# Sheet1.net
KiCad netlist of a schematic drawn in Altium Designer
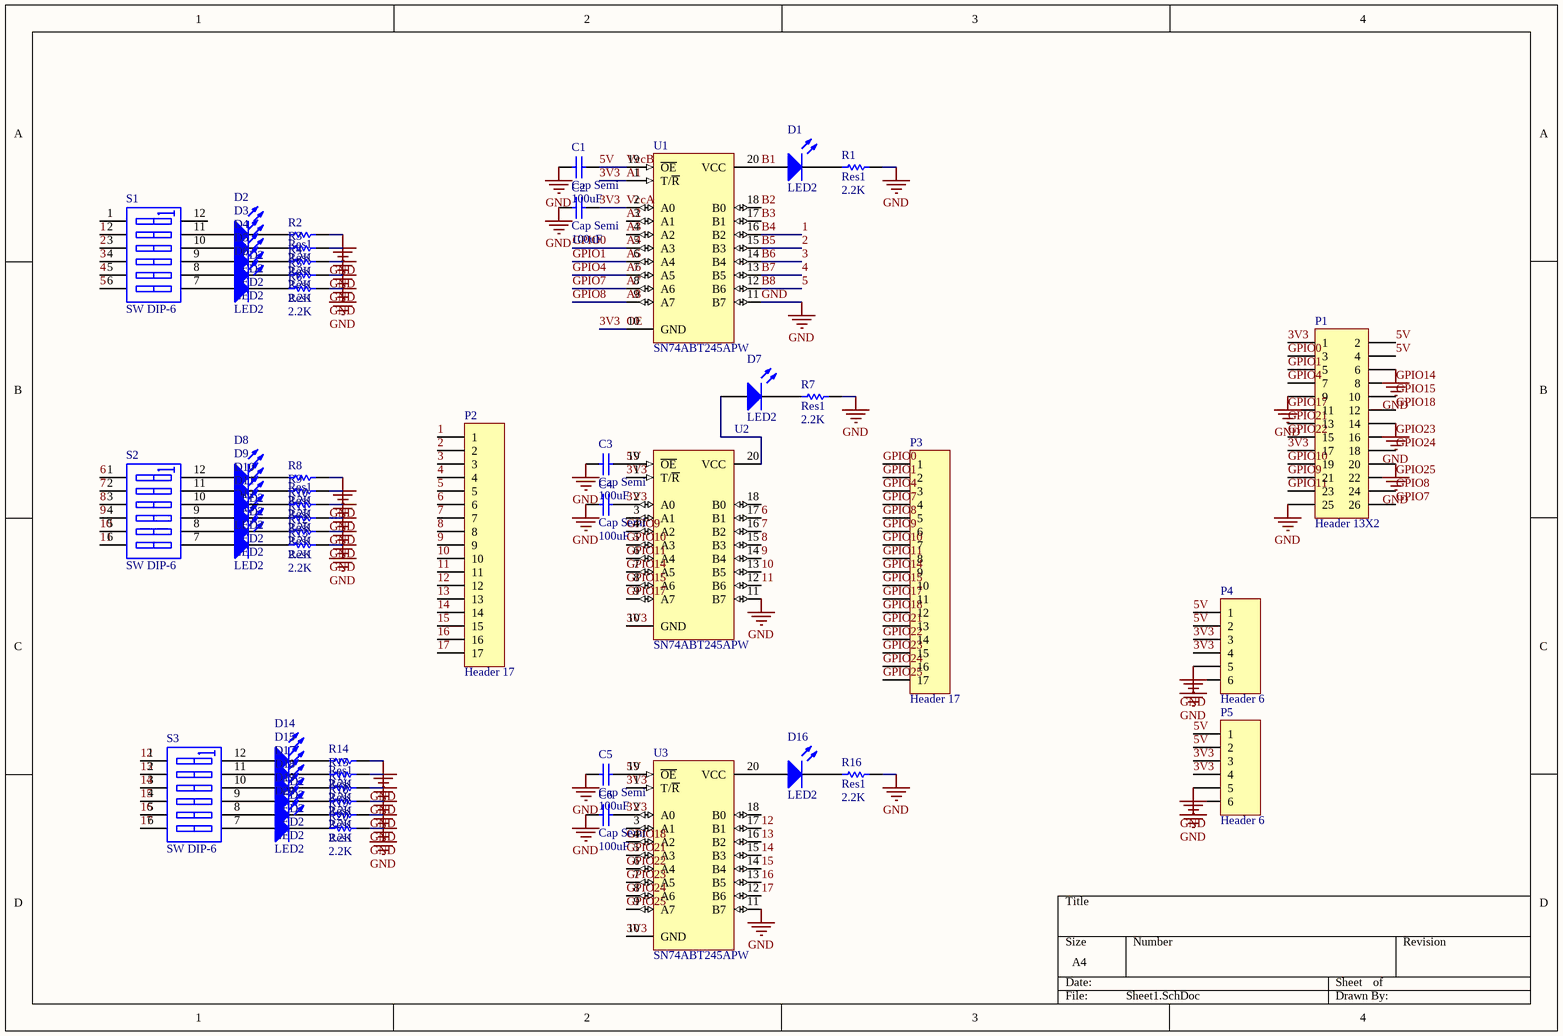
[diagram p0: Sheet1.SchDoc]

(export (version "E")
  (design (tool "Eeschema 10.0.6"))
  (components
    (comp (ref "C1")
      (value "Cap Semi")
      (footprint "C1206")
      (description "Capacitor (Semiconductor SIM Model)")
      (fields (field (name "ALTIUM_VALUE") "100uF") (field (name "PUBLISHER") "Altium Limited"))
      (libsource (lib "Miscellaneous Devices") (part "Cap Semi"))
    )
    (comp (ref "C2")
      (value "Cap Semi")
      (footprint "C1206")
      (description "Capacitor (Semiconductor SIM Model)")
      (fields (field (name "ALTIUM_VALUE") "100uF") (field (name "PUBLISHER") "Altium Limited"))
      (libsource (lib "Miscellaneous Devices") (part "Cap Semi"))
    )
    (comp (ref "C3")
      (value "Cap Semi")
      (footprint "C1206")
      (description "Capacitor (Semiconductor SIM Model)")
      (fields (field (name "ALTIUM_VALUE") "100uF") (field (name "PUBLISHER") "Altium Limited"))
      (libsource (lib "Miscellaneous Devices") (part "Cap Semi"))
    )
    (comp (ref "C4")
      (value "Cap Semi")
      (footprint "C1206")
      (description "Capacitor (Semiconductor SIM Model)")
      (fields (field (name "ALTIUM_VALUE") "100uF") (field (name "PUBLISHER") "Altium Limited"))
      (libsource (lib "Miscellaneous Devices") (part "Cap Semi"))
    )
    (comp (ref "C5")
      (value "Cap Semi")
      (footprint "C1206")
      (description "Capacitor (Semiconductor SIM Model)")
      (fields (field (name "ALTIUM_VALUE") "100uF") (field (name "PUBLISHER") "Altium Limited"))
      (libsource (lib "Miscellaneous Devices") (part "Cap Semi"))
    )
    (comp (ref "C6")
      (value "Cap Semi")
      (footprint "C1206")
      (description "Capacitor (Semiconductor SIM Model)")
      (fields (field (name "ALTIUM_VALUE") "100uF") (field (name "PUBLISHER") "Altium Limited"))
      (libsource (lib "Miscellaneous Devices") (part "Cap Semi"))
    )
    (comp (ref "D1")
      (value "LED2")
      (footprint "0603")
      (description "Typical RED, GREEN, YELLOW, AMBER GaAs LED")
      (fields (field (name "PUBLISHER") "Altium Limited"))
      (libsource (lib "Miscellaneous Devices") (part "LED2"))
    )
    (comp (ref "D2")
      (value "LED2")
      (footprint "0603")
      (description "Typical RED, GREEN, YELLOW, AMBER GaAs LED")
      (fields (field (name "PUBLISHER") "Altium Limited"))
      (libsource (lib "Miscellaneous Devices") (part "LED2"))
    )
    (comp (ref "D3")
      (value "LED2")
      (footprint "0603")
      (description "Typical RED, GREEN, YELLOW, AMBER GaAs LED")
      (fields (field (name "PUBLISHER") "Altium Limited"))
      (libsource (lib "Miscellaneous Devices") (part "LED2"))
    )
    (comp (ref "D4")
      (value "LED2")
      (footprint "0603")
      (description "Typical RED, GREEN, YELLOW, AMBER GaAs LED")
      (fields (field (name "PUBLISHER") "Altium Limited"))
      (libsource (lib "Miscellaneous Devices") (part "LED2"))
    )
    (comp (ref "D5")
      (value "LED2")
      (footprint "0603")
      (description "Typical RED, GREEN, YELLOW, AMBER GaAs LED")
      (fields (field (name "PUBLISHER") "Altium Limited"))
      (libsource (lib "Miscellaneous Devices") (part "LED2"))
    )
    (comp (ref "D6")
      (value "LED2")
      (footprint "0603")
      (description "Typical RED, GREEN, YELLOW, AMBER GaAs LED")
      (fields (field (name "PUBLISHER") "Altium Limited"))
      (libsource (lib "Miscellaneous Devices") (part "LED2"))
    )
    (comp (ref "D7")
      (value "LED2")
      (footprint "0603")
      (description "Typical RED, GREEN, YELLOW, AMBER GaAs LED")
      (fields (field (name "PUBLISHER") "Altium Limited"))
      (libsource (lib "Miscellaneous Devices") (part "LED2"))
    )
    (comp (ref "D8")
      (value "LED2")
      (footprint "0603")
      (description "Typical RED, GREEN, YELLOW, AMBER GaAs LED")
      (fields (field (name "PUBLISHER") "Altium Limited"))
      (libsource (lib "Miscellaneous Devices") (part "LED2"))
    )
    (comp (ref "D9")
      (value "LED2")
      (footprint "0603")
      (description "Typical RED, GREEN, YELLOW, AMBER GaAs LED")
      (fields (field (name "PUBLISHER") "Altium Limited"))
      (libsource (lib "Miscellaneous Devices") (part "LED2"))
    )
    (comp (ref "D10")
      (value "LED2")
      (footprint "0603")
      (description "Typical RED, GREEN, YELLOW, AMBER GaAs LED")
      (fields (field (name "PUBLISHER") "Altium Limited"))
      (libsource (lib "Miscellaneous Devices") (part "LED2"))
    )
    (comp (ref "D11")
      (value "LED2")
      (footprint "0603")
      (description "Typical RED, GREEN, YELLOW, AMBER GaAs LED")
      (fields (field (name "PUBLISHER") "Altium Limited"))
      (libsource (lib "Miscellaneous Devices") (part "LED2"))
    )
    (comp (ref "D12")
      (value "LED2")
      (footprint "0603")
      (description "Typical RED, GREEN, YELLOW, AMBER GaAs LED")
      (fields (field (name "PUBLISHER") "Altium Limited"))
      (libsource (lib "Miscellaneous Devices") (part "LED2"))
    )
    (comp (ref "D13")
      (value "LED2")
      (footprint "0603")
      (description "Typical RED, GREEN, YELLOW, AMBER GaAs LED")
      (fields (field (name "PUBLISHER") "Altium Limited"))
      (libsource (lib "Miscellaneous Devices") (part "LED2"))
    )
    (comp (ref "D14")
      (value "LED2")
      (footprint "0603")
      (description "Typical RED, GREEN, YELLOW, AMBER GaAs LED")
      (fields (field (name "PUBLISHER") "Altium Limited"))
      (libsource (lib "Miscellaneous Devices") (part "LED2"))
    )
    (comp (ref "D15")
      (value "LED2")
      (footprint "0603")
      (description "Typical RED, GREEN, YELLOW, AMBER GaAs LED")
      (fields (field (name "PUBLISHER") "Altium Limited"))
      (libsource (lib "Miscellaneous Devices") (part "LED2"))
    )
    (comp (ref "D16")
      (value "LED2")
      (footprint "0603")
      (description "Typical RED, GREEN, YELLOW, AMBER GaAs LED")
      (fields (field (name "PUBLISHER") "Altium Limited"))
      (libsource (lib "Miscellaneous Devices") (part "LED2"))
    )
    (comp (ref "D17")
      (value "LED2")
      (footprint "0603")
      (description "Typical RED, GREEN, YELLOW, AMBER GaAs LED")
      (fields (field (name "PUBLISHER") "Altium Limited"))
      (libsource (lib "Miscellaneous Devices") (part "LED2"))
    )
    (comp (ref "D18")
      (value "LED2")
      (footprint "0603")
      (description "Typical RED, GREEN, YELLOW, AMBER GaAs LED")
      (fields (field (name "PUBLISHER") "Altium Limited"))
      (libsource (lib "Miscellaneous Devices") (part "LED2"))
    )
    (comp (ref "D19")
      (value "LED2")
      (footprint "0603")
      (description "Typical RED, GREEN, YELLOW, AMBER GaAs LED")
      (fields (field (name "PUBLISHER") "Altium Limited"))
      (libsource (lib "Miscellaneous Devices") (part "LED2"))
    )
    (comp (ref "D20")
      (value "LED2")
      (footprint "0603")
      (description "Typical RED, GREEN, YELLOW, AMBER GaAs LED")
      (fields (field (name "PUBLISHER") "Altium Limited"))
      (libsource (lib "Miscellaneous Devices") (part "LED2"))
    )
    (comp (ref "P1")
      (value "Header 13X2")
      (footprint "HDR2X13")
      (description "Header, 13-Pin, Dual row")
      (fields (field (name "PUBLISHER") "Altium Limited"))
      (libsource (lib "Miscellaneous Connectors") (part "Header 13X2"))
    )
    (comp (ref "P2")
      (value "Header 17")
      (footprint "HDR1X17")
      (description "Header, 17-Pin")
      (fields (field (name "PUBLISHER") "Altium Limited"))
      (libsource (lib "Miscellaneous Connectors") (part "Header 17"))
    )
    (comp (ref "P3")
      (value "Header 17")
      (footprint "HDR1X17")
      (description "Header, 17-Pin")
      (fields (field (name "PUBLISHER") "Altium Limited"))
      (libsource (lib "Miscellaneous Connectors") (part "Header 17"))
    )
    (comp (ref "P4")
      (value "Header 6")
      (footprint "HDR1X6")
      (description "Header, 6-Pin")
      (fields (field (name "PUBLISHER") "Altium Limited"))
      (libsource (lib "Miscellaneous Connectors") (part "Header 6"))
    )
    (comp (ref "P5")
      (value "Header 6")
      (footprint "HDR1X6")
      (description "Header, 6-Pin")
      (fields (field (name "PUBLISHER") "Altium Limited"))
      (libsource (lib "Miscellaneous Connectors") (part "Header 6"))
    )
    (comp (ref "R1")
      (value "Res1")
      (footprint "0603")
      (description "Resistor")
      (fields (field (name "ALTIUM_VALUE") "2.2K") (field (name "PUBLISHER") "Altium Limited"))
      (libsource (lib "Miscellaneous Devices") (part "Res1"))
    )
    (comp (ref "R2")
      (value "Res1")
      (footprint "0603")
      (description "Resistor")
      (fields (field (name "ALTIUM_VALUE") "2.2K") (field (name "PUBLISHER") "Altium Limited"))
      (libsource (lib "Miscellaneous Devices") (part "Res1"))
    )
    (comp (ref "R3")
      (value "Res1")
      (footprint "0603")
      (description "Resistor")
      (fields (field (name "ALTIUM_VALUE") "2.2K") (field (name "PUBLISHER") "Altium Limited"))
      (libsource (lib "Miscellaneous Devices") (part "Res1"))
    )
    (comp (ref "R4")
      (value "Res1")
      (footprint "0603")
      (description "Resistor")
      (fields (field (name "ALTIUM_VALUE") "2.2K") (field (name "PUBLISHER") "Altium Limited"))
      (libsource (lib "Miscellaneous Devices") (part "Res1"))
    )
    (comp (ref "R5")
      (value "Res1")
      (footprint "0603")
      (description "Resistor")
      (fields (field (name "ALTIUM_VALUE") "2.2K") (field (name "PUBLISHER") "Altium Limited"))
      (libsource (lib "Miscellaneous Devices") (part "Res1"))
    )
    (comp (ref "R6")
      (value "Res1")
      (footprint "0603")
      (description "Resistor")
      (fields (field (name "ALTIUM_VALUE") "2.2K") (field (name "PUBLISHER") "Altium Limited"))
      (libsource (lib "Miscellaneous Devices") (part "Res1"))
    )
    (comp (ref "R7")
      (value "Res1")
      (footprint "0603")
      (description "Resistor")
      (fields (field (name "ALTIUM_VALUE") "2.2K") (field (name "PUBLISHER") "Altium Limited"))
      (libsource (lib "Miscellaneous Devices") (part "Res1"))
    )
    (comp (ref "R8")
      (value "Res1")
      (footprint "0603")
      (description "Resistor")
      (fields (field (name "ALTIUM_VALUE") "2.2K") (field (name "PUBLISHER") "Altium Limited"))
      (libsource (lib "Miscellaneous Devices") (part "Res1"))
    )
    (comp (ref "R9")
      (value "Res1")
      (footprint "0603")
      (description "Resistor")
      (fields (field (name "ALTIUM_VALUE") "2.2K") (field (name "PUBLISHER") "Altium Limited"))
      (libsource (lib "Miscellaneous Devices") (part "Res1"))
    )
    (comp (ref "R10")
      (value "Res1")
      (footprint "0603")
      (description "Resistor")
      (fields (field (name "ALTIUM_VALUE") "2.2K") (field (name "PUBLISHER") "Altium Limited"))
      (libsource (lib "Miscellaneous Devices") (part "Res1"))
    )
    (comp (ref "R11")
      (value "Res1")
      (footprint "0603")
      (description "Resistor")
      (fields (field (name "ALTIUM_VALUE") "2.2K") (field (name "PUBLISHER") "Altium Limited"))
      (libsource (lib "Miscellaneous Devices") (part "Res1"))
    )
    (comp (ref "R12")
      (value "Res1")
      (footprint "0603")
      (description "Resistor")
      (fields (field (name "ALTIUM_VALUE") "2.2K") (field (name "PUBLISHER") "Altium Limited"))
      (libsource (lib "Miscellaneous Devices") (part "Res1"))
    )
    (comp (ref "R13")
      (value "Res1")
      (footprint "0603")
      (description "Resistor")
      (fields (field (name "ALTIUM_VALUE") "2.2K") (field (name "PUBLISHER") "Altium Limited"))
      (libsource (lib "Miscellaneous Devices") (part "Res1"))
    )
    (comp (ref "R14")
      (value "Res1")
      (footprint "0603")
      (description "Resistor")
      (fields (field (name "ALTIUM_VALUE") "2.2K") (field (name "PUBLISHER") "Altium Limited"))
      (libsource (lib "Miscellaneous Devices") (part "Res1"))
    )
    (comp (ref "R15")
      (value "Res1")
      (footprint "0603")
      (description "Resistor")
      (fields (field (name "ALTIUM_VALUE") "2.2K") (field (name "PUBLISHER") "Altium Limited"))
      (libsource (lib "Miscellaneous Devices") (part "Res1"))
    )
    (comp (ref "R16")
      (value "Res1")
      (footprint "0603")
      (description "Resistor")
      (fields (field (name "ALTIUM_VALUE") "2.2K") (field (name "PUBLISHER") "Altium Limited"))
      (libsource (lib "Miscellaneous Devices") (part "Res1"))
    )
    (comp (ref "R17")
      (value "Res1")
      (footprint "0603")
      (description "Resistor")
      (fields (field (name "ALTIUM_VALUE") "2.2K") (field (name "PUBLISHER") "Altium Limited"))
      (libsource (lib "Miscellaneous Devices") (part "Res1"))
    )
    (comp (ref "R18")
      (value "Res1")
      (footprint "0603")
      (description "Resistor")
      (fields (field (name "ALTIUM_VALUE") "2.2K") (field (name "PUBLISHER") "Altium Limited"))
      (libsource (lib "Miscellaneous Devices") (part "Res1"))
    )
    (comp (ref "R19")
      (value "Res1")
      (footprint "0603")
      (description "Resistor")
      (fields (field (name "ALTIUM_VALUE") "2.2K") (field (name "PUBLISHER") "Altium Limited"))
      (libsource (lib "Miscellaneous Devices") (part "Res1"))
    )
    (comp (ref "R20")
      (value "Res1")
      (footprint "0603")
      (description "Resistor")
      (fields (field (name "ALTIUM_VALUE") "2.2K") (field (name "PUBLISHER") "Altium Limited"))
      (libsource (lib "Miscellaneous Devices") (part "Res1"))
    )
    (comp (ref "S1")
      (value "SW DIP-6")
      (footprint "DIP-12/SW")
      (description "DIP Switch, 6 Position, SPST")
      (fields (field (name "PUBLISHER") "Altium Limited"))
      (libsource (lib "Miscellaneous Devices") (part "SW DIP-6"))
    )
    (comp (ref "S2")
      (value "SW DIP-6")
      (footprint "DIP-12/SW")
      (description "DIP Switch, 6 Position, SPST")
      (fields (field (name "PUBLISHER") "Altium Limited"))
      (libsource (lib "Miscellaneous Devices") (part "SW DIP-6"))
    )
    (comp (ref "S3")
      (value "SW DIP-6")
      (footprint "DIP-12/SW")
      (description "DIP Switch, 6 Position, SPST")
      (fields (field (name "PUBLISHER") "Altium Limited"))
      (libsource (lib "Miscellaneous Devices") (part "SW DIP-6"))
    )
    (comp (ref "U1")
      (value "SN74ABT245APW")
      (footprint "PW020")
      (description "Octal Bus Transceiver with 3-State Outputs")
      (fields (field (name "PUBLISHER") "Altium Limited"))
      (libsource (lib "TI Interface 8-Bit Line Transceiver") (part "SN74ABT245APW"))
    )
    (comp (ref "U2")
      (value "SN74ABT245APW")
      (footprint "PW020")
      (description "Octal Bus Transceiver with 3-State Outputs")
      (fields (field (name "PUBLISHER") "Altium Limited"))
      (libsource (lib "TI Interface 8-Bit Line Transceiver") (part "SN74ABT245APW"))
    )
    (comp (ref "U3")
      (value "SN74ABT245APW")
      (footprint "PW020")
      (description "Octal Bus Transceiver with 3-State Outputs")
      (fields (field (name "PUBLISHER") "Altium Limited"))
      (libsource (lib "TI Interface 8-Bit Line Transceiver") (part "SN74ABT245APW"))
    )
  )
  (nets
    (net (code "1") (name "/1") (class "Default")
      (node (ref "P2") (pin "1") (pinfunction "1_1") (pintype "passive"))
      (node (ref "S1") (pin "2") (pinfunction "A2_2") (pintype "passive"))
      (node (ref "U1") (pin "16") (pinfunction "B2_16") (pintype "bidirectional"))
    )
    (net (code "2") (name "/2") (class "Default")
      (node (ref "P2") (pin "2") (pinfunction "2_2") (pintype "passive"))
      (node (ref "S1") (pin "3") (pinfunction "A3_3") (pintype "passive"))
      (node (ref "U1") (pin "15") (pinfunction "B3_15") (pintype "bidirectional"))
    )
    (net (code "3") (name "/3") (class "Default")
      (node (ref "P2") (pin "3") (pinfunction "3_3") (pintype "passive"))
      (node (ref "S1") (pin "4") (pinfunction "A4_4") (pintype "passive"))
      (node (ref "U1") (pin "14") (pinfunction "B4_14") (pintype "bidirectional"))
    )
    (net (code "4") (name "/3V3") (class "Default")
      (node (ref "C2") (pin "2") (pinfunction "2_2") (pintype "passive"))
      (node (ref "C4") (pin "2") (pinfunction "2_2") (pintype "passive"))
      (node (ref "C6") (pin "2") (pinfunction "2_2") (pintype "passive"))
      (node (ref "P1") (pin "1") (pinfunction "1_1") (pintype "passive"))
      (node (ref "P1") (pin "17") (pinfunction "17_17") (pintype "passive"))
      (node (ref "P4") (pin "3") (pinfunction "3_3") (pintype "passive"))
      (node (ref "P4") (pin "4") (pinfunction "4_4") (pintype "passive"))
      (node (ref "P5") (pin "3") (pinfunction "3_3") (pintype "passive"))
      (node (ref "P5") (pin "4") (pinfunction "4_4") (pintype "passive"))
      (node (ref "U1") (pin "1") (pinfunction "T/~{R}_1") (pintype "input"))
      (node (ref "U1") (pin "10") (pinfunction "GND_10") (pintype "power_in"))
      (node (ref "U1") (pin "2") (pinfunction "A0_2") (pintype "bidirectional"))
      (node (ref "U2") (pin "1") (pinfunction "T/~{R}_1") (pintype "input"))
      (node (ref "U2") (pin "10") (pinfunction "GND_10") (pintype "power_in"))
      (node (ref "U2") (pin "2") (pinfunction "A0_2") (pintype "bidirectional"))
      (node (ref "U3") (pin "1") (pinfunction "T/~{R}_1") (pintype "input"))
      (node (ref "U3") (pin "10") (pinfunction "GND_10") (pintype "power_in"))
      (node (ref "U3") (pin "2") (pinfunction "A0_2") (pintype "bidirectional"))
    )
    (net (code "5") (name "/4") (class "Default")
      (node (ref "P2") (pin "4") (pinfunction "4_4") (pintype "passive"))
      (node (ref "S1") (pin "5") (pinfunction "A5_5") (pintype "passive"))
      (node (ref "U1") (pin "13") (pinfunction "B5_13") (pintype "bidirectional"))
    )
    (net (code "6") (name "/5") (class "Default")
      (node (ref "P2") (pin "5") (pinfunction "5_5") (pintype "passive"))
      (node (ref "S1") (pin "6") (pinfunction "A6_6") (pintype "passive"))
      (node (ref "U1") (pin "12") (pinfunction "B6_12") (pintype "bidirectional"))
    )
    (net (code "7") (name "/5V") (class "Default")
      (node (ref "C1") (pin "2") (pinfunction "2_2") (pintype "passive"))
      (node (ref "C3") (pin "2") (pinfunction "2_2") (pintype "passive"))
      (node (ref "C5") (pin "2") (pinfunction "2_2") (pintype "passive"))
      (node (ref "P1") (pin "2") (pinfunction "2_2") (pintype "passive"))
      (node (ref "P1") (pin "4") (pinfunction "4_4") (pintype "passive"))
      (node (ref "P4") (pin "1") (pinfunction "1_1") (pintype "passive"))
      (node (ref "P4") (pin "2") (pinfunction "2_2") (pintype "passive"))
      (node (ref "P5") (pin "1") (pinfunction "1_1") (pintype "passive"))
      (node (ref "P5") (pin "2") (pinfunction "2_2") (pintype "passive"))
      (node (ref "U1") (pin "19") (pinfunction "~{OE}_19") (pintype "input"))
      (node (ref "U2") (pin "19") (pinfunction "~{OE}_19") (pintype "input"))
      (node (ref "U3") (pin "19") (pinfunction "~{OE}_19") (pintype "input"))
    )
    (net (code "8") (name "/6") (class "Default")
      (node (ref "P2") (pin "6") (pinfunction "6_6") (pintype "passive"))
      (node (ref "S2") (pin "1") (pinfunction "A1_1") (pintype "passive"))
      (node (ref "U2") (pin "17") (pinfunction "B1_17") (pintype "bidirectional"))
    )
    (net (code "9") (name "/7") (class "Default")
      (node (ref "P2") (pin "7") (pinfunction "7_7") (pintype "passive"))
      (node (ref "S2") (pin "2") (pinfunction "A2_2") (pintype "passive"))
      (node (ref "U2") (pin "16") (pinfunction "B2_16") (pintype "bidirectional"))
    )
    (net (code "10") (name "/8") (class "Default")
      (node (ref "P2") (pin "8") (pinfunction "8_8") (pintype "passive"))
      (node (ref "S2") (pin "3") (pinfunction "A3_3") (pintype "passive"))
      (node (ref "U2") (pin "15") (pinfunction "B3_15") (pintype "bidirectional"))
    )
    (net (code "11") (name "/9") (class "Default")
      (node (ref "P2") (pin "9") (pinfunction "9_9") (pintype "passive"))
      (node (ref "S2") (pin "4") (pinfunction "A4_4") (pintype "passive"))
      (node (ref "U2") (pin "14") (pinfunction "B4_14") (pintype "bidirectional"))
    )
    (net (code "12") (name "/10") (class "Default")
      (node (ref "P2") (pin "10") (pinfunction "10_10") (pintype "passive"))
      (node (ref "S2") (pin "5") (pinfunction "A5_5") (pintype "passive"))
      (node (ref "U2") (pin "13") (pinfunction "B5_13") (pintype "bidirectional"))
    )
    (net (code "13") (name "/11") (class "Default")
      (node (ref "P2") (pin "11") (pinfunction "11_11") (pintype "passive"))
      (node (ref "S2") (pin "6") (pinfunction "A6_6") (pintype "passive"))
      (node (ref "U2") (pin "12") (pinfunction "B6_12") (pintype "bidirectional"))
    )
    (net (code "14") (name "/12") (class "Default")
      (node (ref "P2") (pin "12") (pinfunction "12_12") (pintype "passive"))
      (node (ref "S3") (pin "1") (pinfunction "A1_1") (pintype "passive"))
      (node (ref "U3") (pin "17") (pinfunction "B1_17") (pintype "bidirectional"))
    )
    (net (code "15") (name "/13") (class "Default")
      (node (ref "P2") (pin "13") (pinfunction "13_13") (pintype "passive"))
      (node (ref "S3") (pin "2") (pinfunction "A2_2") (pintype "passive"))
      (node (ref "U3") (pin "16") (pinfunction "B2_16") (pintype "bidirectional"))
    )
    (net (code "16") (name "/14") (class "Default")
      (node (ref "P2") (pin "14") (pinfunction "14_14") (pintype "passive"))
      (node (ref "S3") (pin "3") (pinfunction "A3_3") (pintype "passive"))
      (node (ref "U3") (pin "15") (pinfunction "B3_15") (pintype "bidirectional"))
    )
    (net (code "17") (name "/15") (class "Default")
      (node (ref "P2") (pin "15") (pinfunction "15_15") (pintype "passive"))
      (node (ref "S3") (pin "4") (pinfunction "A4_4") (pintype "passive"))
      (node (ref "U3") (pin "14") (pinfunction "B4_14") (pintype "bidirectional"))
    )
    (net (code "18") (name "/16") (class "Default")
      (node (ref "P2") (pin "16") (pinfunction "16_16") (pintype "passive"))
      (node (ref "S3") (pin "5") (pinfunction "A5_5") (pintype "passive"))
      (node (ref "U3") (pin "13") (pinfunction "B5_13") (pintype "bidirectional"))
    )
    (net (code "19") (name "/17") (class "Default")
      (node (ref "P2") (pin "17") (pinfunction "17_17") (pintype "passive"))
      (node (ref "S3") (pin "6") (pinfunction "A6_6") (pintype "passive"))
      (node (ref "U3") (pin "12") (pinfunction "B6_12") (pintype "bidirectional"))
    )
    (net (code "20") (name "/A2") (class "Default")
      (node (ref "U1") (pin "3") (pinfunction "A1_3") (pintype "bidirectional"))
    )
    (net (code "21") (name "/A3") (class "Default")
      (node (ref "U1") (pin "4") (pinfunction "A2_4") (pintype "bidirectional"))
    )
    (net (code "22") (name "/A4") (class "Default")
      (node (ref "P1") (pin "3") (pinfunction "3_3") (pintype "passive"))
      (node (ref "P3") (pin "1") (pinfunction "1_1") (pintype "passive"))
      (node (ref "U1") (pin "5") (pinfunction "A3_5") (pintype "bidirectional"))
    )
    (net (code "23") (name "/A5") (class "Default")
      (node (ref "P1") (pin "5") (pinfunction "5_5") (pintype "passive"))
      (node (ref "P3") (pin "2") (pinfunction "2_2") (pintype "passive"))
      (node (ref "U1") (pin "6") (pinfunction "A4_6") (pintype "bidirectional"))
    )
    (net (code "24") (name "/A6") (class "Default")
      (node (ref "P1") (pin "7") (pinfunction "7_7") (pintype "passive"))
      (node (ref "P3") (pin "3") (pinfunction "3_3") (pintype "passive"))
      (node (ref "U1") (pin "7") (pinfunction "A5_7") (pintype "bidirectional"))
    )
    (net (code "25") (name "/A7") (class "Default")
      (node (ref "P1") (pin "26") (pinfunction "26_26") (pintype "passive"))
      (node (ref "P3") (pin "4") (pinfunction "4_4") (pintype "passive"))
      (node (ref "U1") (pin "8") (pinfunction "A6_8") (pintype "bidirectional"))
    )
    (net (code "26") (name "/A8") (class "Default")
      (node (ref "P1") (pin "24") (pinfunction "24_24") (pintype "passive"))
      (node (ref "P3") (pin "5") (pinfunction "5_5") (pintype "passive"))
      (node (ref "U1") (pin "9") (pinfunction "A7_9") (pintype "bidirectional"))
    )
    (net (code "27") (name "/B1") (class "Default")
      (node (ref "D1") (pin "1") (pinfunction "A_1") (pintype "passive"))
      (node (ref "U1") (pin "20") (pinfunction "VCC_20") (pintype "power_in"))
    )
    (net (code "28") (name "/B2") (class "Default")
      (node (ref "U1") (pin "18") (pinfunction "B0_18") (pintype "bidirectional"))
    )
    (net (code "29") (name "/B3") (class "Default")
      (node (ref "U1") (pin "17") (pinfunction "B1_17") (pintype "bidirectional"))
    )
    (net (code "30") (name "/GPIO9") (class "Default")
      (node (ref "P1") (pin "21") (pinfunction "21_21") (pintype "passive"))
      (node (ref "P3") (pin "6") (pinfunction "6_6") (pintype "passive"))
      (node (ref "U2") (pin "4") (pinfunction "A2_4") (pintype "bidirectional"))
    )
    (net (code "31") (name "/GPIO10") (class "Default")
      (node (ref "P1") (pin "19") (pinfunction "19_19") (pintype "passive"))
      (node (ref "P3") (pin "7") (pinfunction "7_7") (pintype "passive"))
      (node (ref "U2") (pin "5") (pinfunction "A3_5") (pintype "bidirectional"))
    )
    (net (code "32") (name "/GPIO11") (class "Default")
      (node (ref "P1") (pin "23") (pinfunction "23_23") (pintype "passive"))
      (node (ref "P3") (pin "8") (pinfunction "8_8") (pintype "passive"))
      (node (ref "U2") (pin "6") (pinfunction "A4_6") (pintype "bidirectional"))
    )
    (net (code "33") (name "/GPIO14") (class "Default")
      (node (ref "P1") (pin "8") (pinfunction "8_8") (pintype "passive"))
      (node (ref "P3") (pin "9") (pinfunction "9_9") (pintype "passive"))
      (node (ref "U2") (pin "7") (pinfunction "A5_7") (pintype "bidirectional"))
    )
    (net (code "34") (name "/GPIO15") (class "Default")
      (node (ref "P1") (pin "10") (pinfunction "10_10") (pintype "passive"))
      (node (ref "P3") (pin "10") (pinfunction "10_10") (pintype "passive"))
      (node (ref "U2") (pin "8") (pinfunction "A6_8") (pintype "bidirectional"))
    )
    (net (code "35") (name "/GPIO17") (class "Default")
      (node (ref "P1") (pin "11") (pinfunction "11_11") (pintype "passive"))
      (node (ref "P3") (pin "11") (pinfunction "11_11") (pintype "passive"))
      (node (ref "U2") (pin "9") (pinfunction "A7_9") (pintype "bidirectional"))
    )
    (net (code "36") (name "/GPIO18") (class "Default")
      (node (ref "P1") (pin "12") (pinfunction "12_12") (pintype "passive"))
      (node (ref "P3") (pin "12") (pinfunction "12_12") (pintype "passive"))
      (node (ref "U3") (pin "4") (pinfunction "A2_4") (pintype "bidirectional"))
    )
    (net (code "37") (name "/GPIO21") (class "Default")
      (node (ref "P1") (pin "13") (pinfunction "13_13") (pintype "passive"))
      (node (ref "P3") (pin "13") (pinfunction "13_13") (pintype "passive"))
      (node (ref "U3") (pin "5") (pinfunction "A3_5") (pintype "bidirectional"))
    )
    (net (code "38") (name "/GPIO22") (class "Default")
      (node (ref "P1") (pin "15") (pinfunction "15_15") (pintype "passive"))
      (node (ref "P3") (pin "14") (pinfunction "14_14") (pintype "passive"))
      (node (ref "U3") (pin "6") (pinfunction "A4_6") (pintype "bidirectional"))
    )
    (net (code "39") (name "/GPIO23") (class "Default")
      (node (ref "P1") (pin "16") (pinfunction "16_16") (pintype "passive"))
      (node (ref "P3") (pin "15") (pinfunction "15_15") (pintype "passive"))
      (node (ref "U3") (pin "7") (pinfunction "A5_7") (pintype "bidirectional"))
    )
    (net (code "40") (name "/GPIO24") (class "Default")
      (node (ref "P1") (pin "18") (pinfunction "18_18") (pintype "passive"))
      (node (ref "P3") (pin "16") (pinfunction "16_16") (pintype "passive"))
      (node (ref "U3") (pin "8") (pinfunction "A6_8") (pintype "bidirectional"))
    )
    (net (code "41") (name "/GPIO25") (class "Default")
      (node (ref "P1") (pin "22") (pinfunction "22_22") (pintype "passive"))
      (node (ref "P3") (pin "17") (pinfunction "17_17") (pintype "passive"))
      (node (ref "U3") (pin "9") (pinfunction "A7_9") (pintype "bidirectional"))
    )
    (net (code "42") (name "GND") (class "Default")
      (node (ref "C1") (pin "1") (pinfunction "1_1") (pintype "passive"))
      (node (ref "C2") (pin "1") (pinfunction "1_1") (pintype "passive"))
      (node (ref "C3") (pin "1") (pinfunction "1_1") (pintype "passive"))
      (node (ref "C4") (pin "1") (pinfunction "1_1") (pintype "passive"))
      (node (ref "C5") (pin "1") (pinfunction "1_1") (pintype "passive"))
      (node (ref "C6") (pin "1") (pinfunction "1_1") (pintype "passive"))
      (node (ref "P1") (pin "14") (pinfunction "14_14") (pintype "passive"))
      (node (ref "P1") (pin "20") (pinfunction "20_20") (pintype "passive"))
      (node (ref "P1") (pin "25") (pinfunction "25_25") (pintype "passive"))
      (node (ref "P1") (pin "6") (pinfunction "6_6") (pintype "passive"))
      (node (ref "P1") (pin "9") (pinfunction "9_9") (pintype "passive"))
      (node (ref "P4") (pin "5") (pinfunction "5_5") (pintype "passive"))
      (node (ref "P4") (pin "6") (pinfunction "6_6") (pintype "passive"))
      (node (ref "P5") (pin "5") (pinfunction "5_5") (pintype "passive"))
      (node (ref "P5") (pin "6") (pinfunction "6_6") (pintype "passive"))
      (node (ref "R1") (pin "2") (pinfunction "2_2") (pintype "passive"))
      (node (ref "R10") (pin "2") (pinfunction "2_2") (pintype "passive"))
      (node (ref "R11") (pin "2") (pinfunction "2_2") (pintype "passive"))
      (node (ref "R12") (pin "2") (pinfunction "2_2") (pintype "passive"))
      (node (ref "R13") (pin "2") (pinfunction "2_2") (pintype "passive"))
      (node (ref "R14") (pin "2") (pinfunction "2_2") (pintype "passive"))
      (node (ref "R15") (pin "2") (pinfunction "2_2") (pintype "passive"))
      (node (ref "R16") (pin "2") (pinfunction "2_2") (pintype "passive"))
      (node (ref "R17") (pin "2") (pinfunction "2_2") (pintype "passive"))
      (node (ref "R18") (pin "2") (pinfunction "2_2") (pintype "passive"))
      (node (ref "R19") (pin "2") (pinfunction "2_2") (pintype "passive"))
      (node (ref "R2") (pin "2") (pinfunction "2_2") (pintype "passive"))
      (node (ref "R20") (pin "2") (pinfunction "2_2") (pintype "passive"))
      (node (ref "R3") (pin "2") (pinfunction "2_2") (pintype "passive"))
      (node (ref "R4") (pin "2") (pinfunction "2_2") (pintype "passive"))
      (node (ref "R5") (pin "2") (pinfunction "2_2") (pintype "passive"))
      (node (ref "R6") (pin "2") (pinfunction "2_2") (pintype "passive"))
      (node (ref "R7") (pin "2") (pinfunction "2_2") (pintype "passive"))
      (node (ref "R8") (pin "2") (pinfunction "2_2") (pintype "passive"))
      (node (ref "R9") (pin "2") (pinfunction "2_2") (pintype "passive"))
      (node (ref "U1") (pin "11") (pinfunction "B7_11") (pintype "bidirectional"))
      (node (ref "U2") (pin "11") (pinfunction "B7_11") (pintype "bidirectional"))
      (node (ref "U3") (pin "11") (pinfunction "B7_11") (pintype "bidirectional"))
    )
    (net (code "43") (name "Net-(D1-K)") (class "Default")
      (node (ref "D1") (pin "2") (pinfunction "K_2") (pintype "passive"))
      (node (ref "R1") (pin "1") (pinfunction "1_1") (pintype "passive"))
    )
    (net (code "44") (name "Net-(D2-A)") (class "Default")
      (node (ref "D2") (pin "1") (pinfunction "A_1") (pintype "passive"))
      (node (ref "S1") (pin "11") (pinfunction "B2_11") (pintype "passive"))
    )
    (net (code "45") (name "Net-(D2-K)") (class "Default")
      (node (ref "D2") (pin "2") (pinfunction "K_2") (pintype "passive"))
      (node (ref "R2") (pin "1") (pinfunction "1_1") (pintype "passive"))
    )
    (net (code "46") (name "Net-(D3-A)") (class "Default")
      (node (ref "D3") (pin "1") (pinfunction "A_1") (pintype "passive"))
      (node (ref "S1") (pin "10") (pinfunction "B3_10") (pintype "passive"))
    )
    (net (code "47") (name "Net-(D3-K)") (class "Default")
      (node (ref "D3") (pin "2") (pinfunction "K_2") (pintype "passive"))
      (node (ref "R3") (pin "1") (pinfunction "1_1") (pintype "passive"))
    )
    (net (code "48") (name "Net-(D4-A)") (class "Default")
      (node (ref "D4") (pin "1") (pinfunction "A_1") (pintype "passive"))
      (node (ref "S1") (pin "9") (pinfunction "B4_9") (pintype "passive"))
    )
    (net (code "49") (name "Net-(D4-K)") (class "Default")
      (node (ref "D4") (pin "2") (pinfunction "K_2") (pintype "passive"))
      (node (ref "R4") (pin "1") (pinfunction "1_1") (pintype "passive"))
    )
    (net (code "50") (name "Net-(D5-A)") (class "Default")
      (node (ref "D5") (pin "1") (pinfunction "A_1") (pintype "passive"))
      (node (ref "S1") (pin "8") (pinfunction "B5_8") (pintype "passive"))
    )
    (net (code "51") (name "Net-(D5-K)") (class "Default")
      (node (ref "D5") (pin "2") (pinfunction "K_2") (pintype "passive"))
      (node (ref "R5") (pin "1") (pinfunction "1_1") (pintype "passive"))
    )
    (net (code "52") (name "Net-(D6-A)") (class "Default")
      (node (ref "D6") (pin "1") (pinfunction "A_1") (pintype "passive"))
      (node (ref "S1") (pin "7") (pinfunction "B6_7") (pintype "passive"))
    )
    (net (code "53") (name "Net-(D6-K)") (class "Default")
      (node (ref "D6") (pin "2") (pinfunction "K_2") (pintype "passive"))
      (node (ref "R6") (pin "1") (pinfunction "1_1") (pintype "passive"))
    )
    (net (code "54") (name "Net-(D7-A)") (class "Default")
      (node (ref "D7") (pin "1") (pinfunction "A_1") (pintype "passive"))
      (node (ref "U2") (pin "20") (pinfunction "VCC_20") (pintype "power_in"))
    )
    (net (code "55") (name "Net-(D7-K)") (class "Default")
      (node (ref "D7") (pin "2") (pinfunction "K_2") (pintype "passive"))
      (node (ref "R7") (pin "1") (pinfunction "1_1") (pintype "passive"))
    )
    (net (code "56") (name "Net-(D8-A)") (class "Default")
      (node (ref "D8") (pin "1") (pinfunction "A_1") (pintype "passive"))
      (node (ref "S2") (pin "12") (pinfunction "B1_12") (pintype "passive"))
    )
    (net (code "57") (name "Net-(D8-K)") (class "Default")
      (node (ref "D8") (pin "2") (pinfunction "K_2") (pintype "passive"))
      (node (ref "R8") (pin "1") (pinfunction "1_1") (pintype "passive"))
    )
    (net (code "58") (name "Net-(D9-A)") (class "Default")
      (node (ref "D9") (pin "1") (pinfunction "A_1") (pintype "passive"))
      (node (ref "S2") (pin "11") (pinfunction "B2_11") (pintype "passive"))
    )
    (net (code "59") (name "Net-(D9-K)") (class "Default")
      (node (ref "D9") (pin "2") (pinfunction "K_2") (pintype "passive"))
      (node (ref "R9") (pin "1") (pinfunction "1_1") (pintype "passive"))
    )
    (net (code "60") (name "Net-(D10-A)") (class "Default")
      (node (ref "D10") (pin "1") (pinfunction "A_1") (pintype "passive"))
      (node (ref "S2") (pin "10") (pinfunction "B3_10") (pintype "passive"))
    )
    (net (code "61") (name "Net-(D10-K)") (class "Default")
      (node (ref "D10") (pin "2") (pinfunction "K_2") (pintype "passive"))
      (node (ref "R10") (pin "1") (pinfunction "1_1") (pintype "passive"))
    )
    (net (code "62") (name "Net-(D11-A)") (class "Default")
      (node (ref "D11") (pin "1") (pinfunction "A_1") (pintype "passive"))
      (node (ref "S2") (pin "9") (pinfunction "B4_9") (pintype "passive"))
    )
    (net (code "63") (name "Net-(D11-K)") (class "Default")
      (node (ref "D11") (pin "2") (pinfunction "K_2") (pintype "passive"))
      (node (ref "R11") (pin "1") (pinfunction "1_1") (pintype "passive"))
    )
    (net (code "64") (name "Net-(D12-A)") (class "Default")
      (node (ref "D12") (pin "1") (pinfunction "A_1") (pintype "passive"))
      (node (ref "S2") (pin "8") (pinfunction "B5_8") (pintype "passive"))
    )
    (net (code "65") (name "Net-(D12-K)") (class "Default")
      (node (ref "D12") (pin "2") (pinfunction "K_2") (pintype "passive"))
      (node (ref "R12") (pin "1") (pinfunction "1_1") (pintype "passive"))
    )
    (net (code "66") (name "Net-(D13-A)") (class "Default")
      (node (ref "D13") (pin "1") (pinfunction "A_1") (pintype "passive"))
      (node (ref "S2") (pin "7") (pinfunction "B6_7") (pintype "passive"))
    )
    (net (code "67") (name "Net-(D13-K)") (class "Default")
      (node (ref "D13") (pin "2") (pinfunction "K_2") (pintype "passive"))
      (node (ref "R13") (pin "1") (pinfunction "1_1") (pintype "passive"))
    )
    (net (code "68") (name "Net-(D14-A)") (class "Default")
      (node (ref "D14") (pin "1") (pinfunction "A_1") (pintype "passive"))
      (node (ref "S3") (pin "12") (pinfunction "B1_12") (pintype "passive"))
    )
    (net (code "69") (name "Net-(D14-K)") (class "Default")
      (node (ref "D14") (pin "2") (pinfunction "K_2") (pintype "passive"))
      (node (ref "R14") (pin "1") (pinfunction "1_1") (pintype "passive"))
    )
    (net (code "70") (name "Net-(D15-A)") (class "Default")
      (node (ref "D15") (pin "1") (pinfunction "A_1") (pintype "passive"))
      (node (ref "S3") (pin "11") (pinfunction "B2_11") (pintype "passive"))
    )
    (net (code "71") (name "Net-(D15-K)") (class "Default")
      (node (ref "D15") (pin "2") (pinfunction "K_2") (pintype "passive"))
      (node (ref "R15") (pin "1") (pinfunction "1_1") (pintype "passive"))
    )
    (net (code "72") (name "Net-(D16-A)") (class "Default")
      (node (ref "D16") (pin "1") (pinfunction "A_1") (pintype "passive"))
      (node (ref "U3") (pin "20") (pinfunction "VCC_20") (pintype "power_in"))
    )
    (net (code "73") (name "Net-(D16-K)") (class "Default")
      (node (ref "D16") (pin "2") (pinfunction "K_2") (pintype "passive"))
      (node (ref "R16") (pin "1") (pinfunction "1_1") (pintype "passive"))
    )
    (net (code "74") (name "Net-(D17-A)") (class "Default")
      (node (ref "D17") (pin "1") (pinfunction "A_1") (pintype "passive"))
      (node (ref "S3") (pin "10") (pinfunction "B3_10") (pintype "passive"))
    )
    (net (code "75") (name "Net-(D17-K)") (class "Default")
      (node (ref "D17") (pin "2") (pinfunction "K_2") (pintype "passive"))
      (node (ref "R17") (pin "1") (pinfunction "1_1") (pintype "passive"))
    )
    (net (code "76") (name "Net-(D18-A)") (class "Default")
      (node (ref "D18") (pin "1") (pinfunction "A_1") (pintype "passive"))
      (node (ref "S3") (pin "9") (pinfunction "B4_9") (pintype "passive"))
    )
    (net (code "77") (name "Net-(D18-K)") (class "Default")
      (node (ref "D18") (pin "2") (pinfunction "K_2") (pintype "passive"))
      (node (ref "R18") (pin "1") (pinfunction "1_1") (pintype "passive"))
    )
    (net (code "78") (name "Net-(D19-A)") (class "Default")
      (node (ref "D19") (pin "1") (pinfunction "A_1") (pintype "passive"))
      (node (ref "S3") (pin "8") (pinfunction "B5_8") (pintype "passive"))
    )
    (net (code "79") (name "Net-(D19-K)") (class "Default")
      (node (ref "D19") (pin "2") (pinfunction "K_2") (pintype "passive"))
      (node (ref "R19") (pin "1") (pinfunction "1_1") (pintype "passive"))
    )
    (net (code "80") (name "Net-(D20-A)") (class "Default")
      (node (ref "D20") (pin "1") (pinfunction "A_1") (pintype "passive"))
      (node (ref "S3") (pin "7") (pinfunction "B6_7") (pintype "passive"))
    )
    (net (code "81") (name "Net-(D20-K)") (class "Default")
      (node (ref "D20") (pin "2") (pinfunction "K_2") (pintype "passive"))
      (node (ref "R20") (pin "1") (pinfunction "1_1") (pintype "passive"))
    )
    (net (code "82") (name "unconnected-(S1-A1-Pad1)") (class "Default")
      (node (ref "S1") (pin "1") (pinfunction "A1_1") (pintype "passive"))
    )
    (net (code "83") (name "unconnected-(S1-B1-Pad12)") (class "Default")
      (node (ref "S1") (pin "12") (pinfunction "B1_12") (pintype "passive"))
    )
    (net (code "84") (name "unconnected-(U2-A1-Pad3)") (class "Default")
      (node (ref "U2") (pin "3") (pinfunction "A1_3") (pintype "bidirectional"))
    )
    (net (code "85") (name "unconnected-(U2-B0-Pad18)") (class "Default")
      (node (ref "U2") (pin "18") (pinfunction "B0_18") (pintype "bidirectional"))
    )
    (net (code "86") (name "unconnected-(U3-A1-Pad3)") (class "Default")
      (node (ref "U3") (pin "3") (pinfunction "A1_3") (pintype "bidirectional"))
    )
    (net (code "87") (name "unconnected-(U3-B0-Pad18)") (class "Default")
      (node (ref "U3") (pin "18") (pinfunction "B0_18") (pintype "bidirectional"))
    )
  )
)
